# kul_rev0.net
KiCad netlist of a schematic drawn in EAGLE
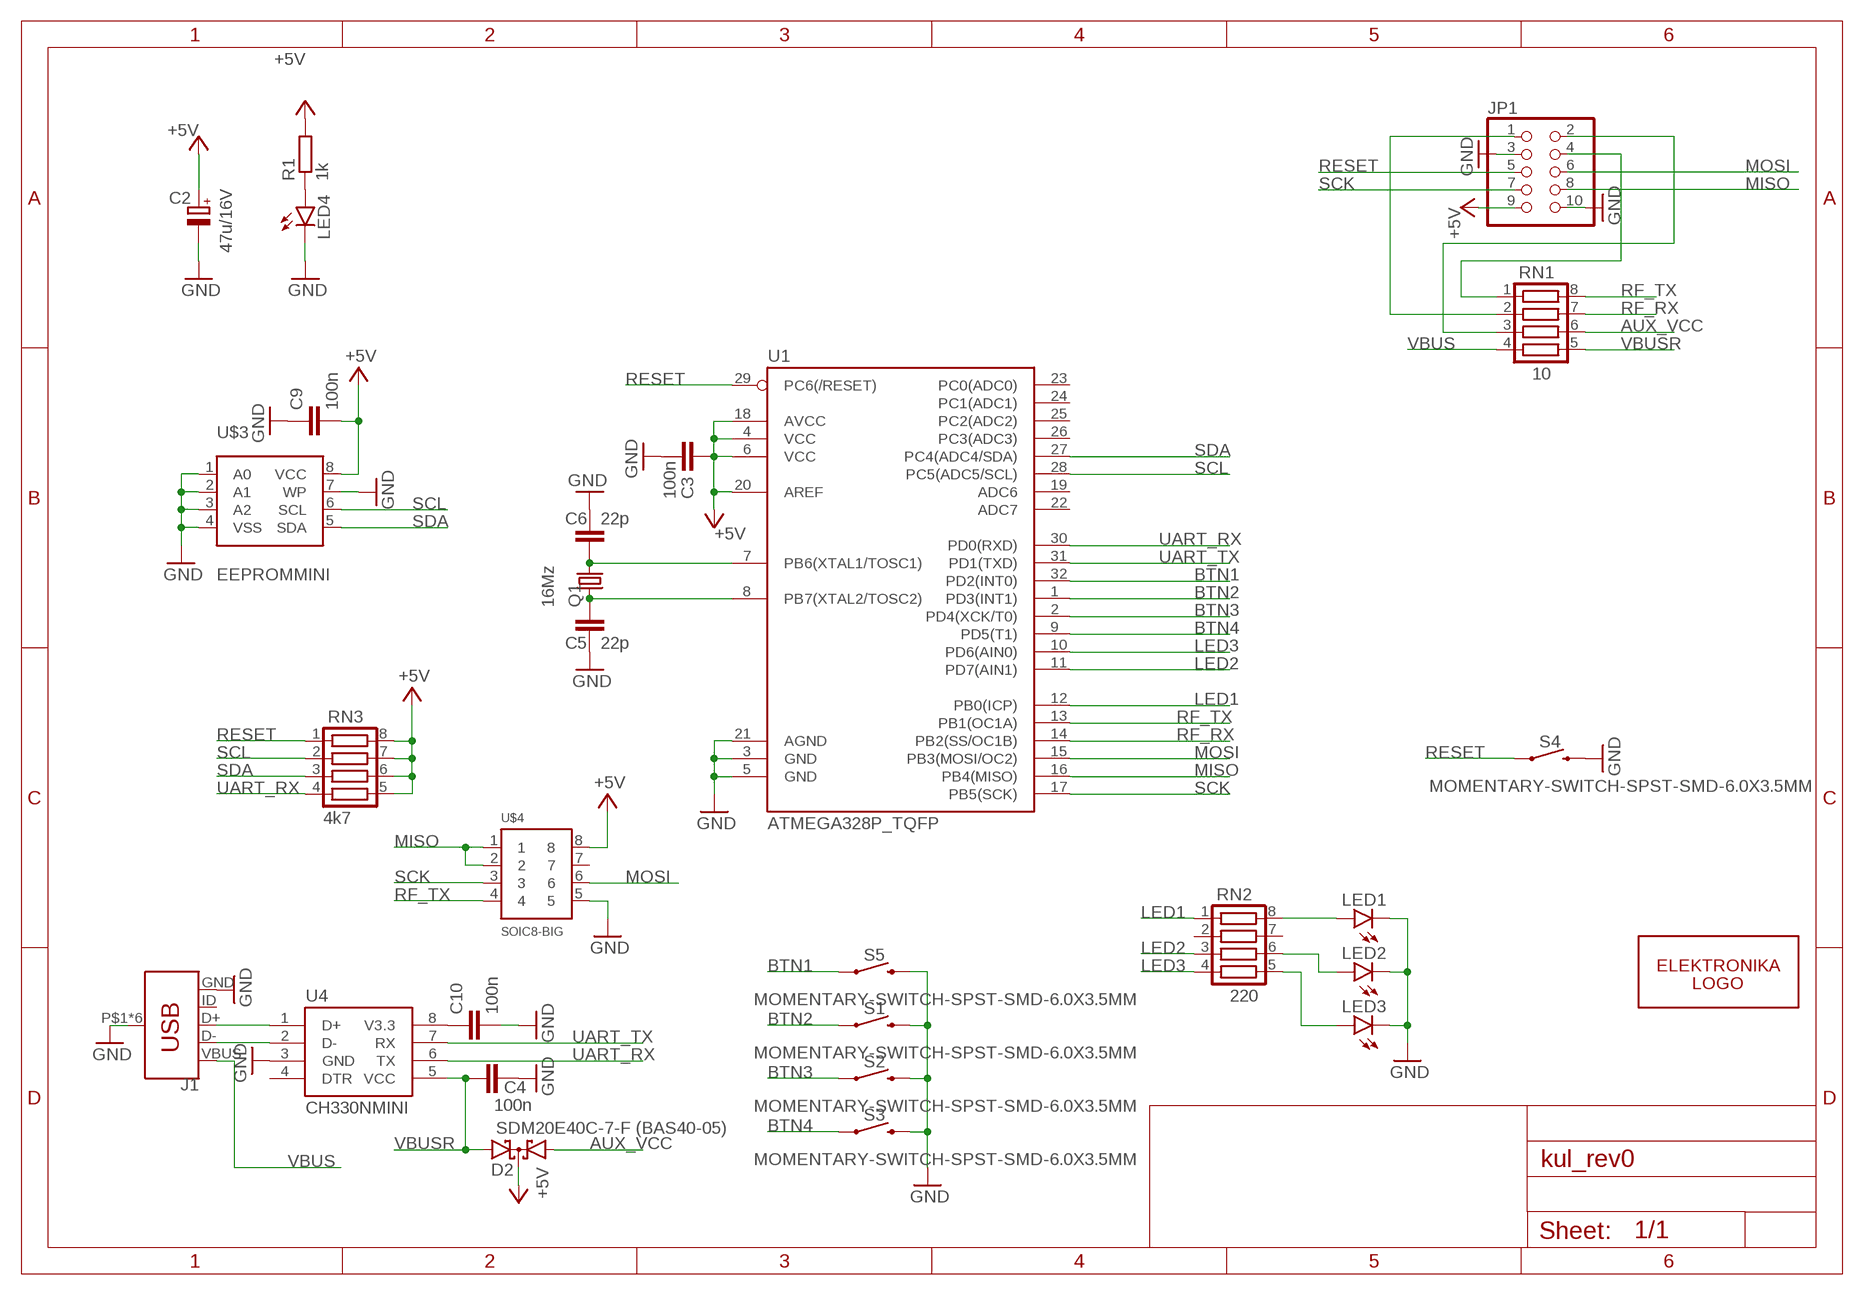
[diagram p0: schematic, sheet 1]

(export (version "E")
  (design (tool "Eeschema 10.0.6"))
  (components
    (comp (ref "C2")
      (value "47u/16V")
      (footprint "eagle-import:CT6032")
      (libsource (lib "eagle-import") (part "CPOL-EUCT6032"))
    )
    (comp (ref "C3")
      (value "100n")
      (footprint "eagle-import:C0603")
      (libsource (lib "eagle-import") (part "C-EUC0603"))
    )
    (comp (ref "C4")
      (value "100n")
      (footprint "eagle-import:C0603")
      (libsource (lib "eagle-import") (part "C-EUC0603"))
    )
    (comp (ref "C5")
      (value "22p")
      (footprint "eagle-import:C0603")
      (libsource (lib "eagle-import") (part "C-EUC0603"))
    )
    (comp (ref "C6")
      (value "22p")
      (footprint "eagle-import:C0603")
      (libsource (lib "eagle-import") (part "C-EUC0603"))
    )
    (comp (ref "C9")
      (value "100n")
      (footprint "eagle-import:C0603")
      (libsource (lib "eagle-import") (part "C-EUC0603"))
    )
    (comp (ref "C10")
      (value "100n")
      (footprint "eagle-import:C0603")
      (libsource (lib "eagle-import") (part "C-EUC0603"))
    )
    (comp (ref "D2")
      (value "SDM20E40C-7-F (BAS40-05)")
      (footprint "eagle-import:SOT23")
      (libsource (lib "eagle-import") (part "BAS40-05"))
    )
    (comp (ref "J1")
      (value "USB_MICRO-BLCSC")
      (footprint "eagle-import:C40951_USB")
      (libsource (lib "eagle-import") (part "USB_MICRO-BLCSC"))
    )
    (comp (ref "JP1")
      (value "PINHD-2X5/90")
      (footprint "eagle-import:2X05_90")
      (libsource (lib "eagle-import") (part "PINHD-2X5/90"))
    )
    (comp (ref "LED1")
      (value "LEDCHIP-LED0805")
      (footprint "eagle-import:CHIP-LED0805")
      (libsource (lib "eagle-import") (part "LEDCHIP-LED0805"))
    )
    (comp (ref "LED2")
      (value "LEDCHIP-LED0805")
      (footprint "eagle-import:CHIP-LED0805")
      (libsource (lib "eagle-import") (part "LEDCHIP-LED0805"))
    )
    (comp (ref "LED3")
      (value "LEDCHIP-LED0805")
      (footprint "eagle-import:CHIP-LED0805")
      (libsource (lib "eagle-import") (part "LEDCHIP-LED0805"))
    )
    (comp (ref "LED4")
      (value "LEDCHIP-LED0805")
      (footprint "eagle-import:CHIP-LED0805")
      (libsource (lib "eagle-import") (part "LEDCHIP-LED0805"))
    )
    (comp (ref "Q1")
      (value "16Mz")
      (footprint "eagle-import:3.2X2.5_KX-7")
      (libsource (lib "eagle-import") (part "KX-7"))
    )
    (comp (ref "R1")
      (value "1k")
      (footprint "eagle-import:R0603")
      (libsource (lib "eagle-import") (part "R-EU_R0603"))
    )
    (comp (ref "RN1")
      (value "10")
      (footprint "eagle-import:CTS742C083")
      (libsource (lib "eagle-import") (part "CTS742C083"))
    )
    (comp (ref "RN2")
      (value "220")
      (footprint "eagle-import:CTS742C083")
      (libsource (lib "eagle-import") (part "CTS742C083"))
    )
    (comp (ref "RN3")
      (value "4k7")
      (footprint "eagle-import:CTS742C083")
      (libsource (lib "eagle-import") (part "CTS742C083"))
    )
    (comp (ref "S1")
      (value "MOMENTARY-SWITCH-SPST-SMD-6.0X3.5MM")
      (footprint "eagle-import:TACTILE_SWITCH_SMD_6.0X3.5MM")
      (libsource (lib "eagle-import") (part "MOMENTARY-SWITCH-SPST-SMD-6.0X3.5MM"))
    )
    (comp (ref "S2")
      (value "MOMENTARY-SWITCH-SPST-SMD-6.0X3.5MM")
      (footprint "eagle-import:TACTILE_SWITCH_SMD_6.0X3.5MM")
      (libsource (lib "eagle-import") (part "MOMENTARY-SWITCH-SPST-SMD-6.0X3.5MM"))
    )
    (comp (ref "S3")
      (value "MOMENTARY-SWITCH-SPST-SMD-6.0X3.5MM")
      (footprint "eagle-import:TACTILE_SWITCH_SMD_6.0X3.5MM")
      (libsource (lib "eagle-import") (part "MOMENTARY-SWITCH-SPST-SMD-6.0X3.5MM"))
    )
    (comp (ref "S4")
      (value "MOMENTARY-SWITCH-SPST-SMD-6.0X3.5MM")
      (footprint "eagle-import:TACTILE_SWITCH_SMD_6.0X3.5MM")
      (libsource (lib "eagle-import") (part "MOMENTARY-SWITCH-SPST-SMD-6.0X3.5MM"))
    )
    (comp (ref "S5")
      (value "MOMENTARY-SWITCH-SPST-SMD-6.0X3.5MM")
      (footprint "eagle-import:TACTILE_SWITCH_SMD_6.0X3.5MM")
      (libsource (lib "eagle-import") (part "MOMENTARY-SWITCH-SPST-SMD-6.0X3.5MM"))
    )
    (comp (ref "U$3")
      (value "EEPROMMINI")
      (footprint "eagle-import:SOIC8_MINI")
      (libsource (lib "eagle-import") (part "EEPROMMINI"))
    )
    (comp (ref "U$4")
      (value "SOIC8-BIG")
      (footprint "eagle-import:SOIC8_BIG")
      (libsource (lib "eagle-import") (part "SOIC8-BIG"))
    )
    (comp (ref "U$6")
      (value "ELEKTRONIKA_BA_ELEBA_LOGO")
      (footprint "eagle-import:ELEKTRONIKA_BA_ELEBALOGO_ELEBALOGO_B_122")
      (libsource (lib "eagle-import") (part "ELEKTRONIKA_BA_ELEBA_LOGO"))
    )
    (comp (ref "U1")
      (value "ATMEGA328P_TQFP")
      (footprint "eagle-import:TQFP32-08")
      (libsource (lib "eagle-import") (part "ATMEGA328P_TQFP"))
    )
    (comp (ref "U4")
      (value "CH330NMINI")
      (footprint "eagle-import:SOIC8_MINI")
      (libsource (lib "eagle-import") (part "CH330NMINI"))
    )
  )
  (nets
    (net (code "1") (name "+5V") (class "Default")
      (node (ref "C2") (pin "+") (pinfunction "+_+") (pintype "passive"))
      (node (ref "C3") (pin "2") (pinfunction "2_2") (pintype "passive"))
      (node (ref "C9") (pin "2") (pinfunction "2_2") (pintype "passive"))
      (node (ref "D2") (pin "3") (pinfunction "C_3") (pintype "passive"))
      (node (ref "JP1") (pin "9") (pinfunction "9_9") (pintype "passive"))
      (node (ref "R1") (pin "2") (pinfunction "2_2") (pintype "passive"))
      (node (ref "RN3") (pin "5") (pinfunction "5_5") (pintype "passive"))
      (node (ref "RN3") (pin "6") (pinfunction "6_6") (pintype "passive"))
      (node (ref "RN3") (pin "7") (pinfunction "7_7") (pintype "passive"))
      (node (ref "RN3") (pin "8") (pinfunction "8_8") (pintype "passive"))
      (node (ref "U$3") (pin "8") (pinfunction "VCC_8") (pintype "bidirectional"))
      (node (ref "U$4") (pin "8") (pinfunction "8_8") (pintype "bidirectional"))
      (node (ref "U1") (pin "18") (pinfunction "AVCC_18") (pintype "bidirectional"))
      (node (ref "U1") (pin "20") (pinfunction "AREF_20") (pintype "bidirectional"))
      (node (ref "U1") (pin "4") (pinfunction "VCC_4") (pintype "bidirectional"))
      (node (ref "U1") (pin "6") (pinfunction "VCC_6") (pintype "bidirectional"))
    )
    (net (code "2") (name "/AUX_VCC") (class "Default")
      (node (ref "D2") (pin "1") (pinfunction "A1_1") (pintype "passive"))
      (node (ref "RN1") (pin "6") (pinfunction "6_6") (pintype "passive"))
    )
    (net (code "3") (name "/BTN1") (class "Default")
      (node (ref "S5") (pin "1") (pinfunction "1_1") (pintype "passive"))
      (node (ref "U1") (pin "32") (pinfunction "PD2(INT0)_32") (pintype "bidirectional"))
    )
    (net (code "4") (name "/BTN2") (class "Default")
      (node (ref "S1") (pin "1") (pinfunction "1_1") (pintype "passive"))
      (node (ref "U1") (pin "1") (pinfunction "PD3(INT1)_1") (pintype "bidirectional"))
    )
    (net (code "5") (name "/BTN3") (class "Default")
      (node (ref "S2") (pin "1") (pinfunction "1_1") (pintype "passive"))
      (node (ref "U1") (pin "2") (pinfunction "PD4(XCK/T0)_2") (pintype "bidirectional"))
    )
    (net (code "6") (name "/BTN4") (class "Default")
      (node (ref "S3") (pin "1") (pinfunction "1_1") (pintype "passive"))
      (node (ref "U1") (pin "9") (pinfunction "PD5(T1)_9") (pintype "bidirectional"))
    )
    (net (code "7") (name "/LED1") (class "Default")
      (node (ref "RN2") (pin "1") (pinfunction "1_1") (pintype "passive"))
      (node (ref "U1") (pin "12") (pinfunction "PB0(ICP)_12") (pintype "bidirectional"))
    )
    (net (code "8") (name "/LED2") (class "Default")
      (node (ref "RN2") (pin "3") (pinfunction "3_3") (pintype "passive"))
      (node (ref "U1") (pin "11") (pinfunction "PD7(AIN1)_11") (pintype "bidirectional"))
    )
    (net (code "9") (name "/LED3") (class "Default")
      (node (ref "RN2") (pin "4") (pinfunction "4_4") (pintype "passive"))
      (node (ref "U1") (pin "10") (pinfunction "PD6(AIN0)_10") (pintype "bidirectional"))
    )
    (net (code "10") (name "/MISO") (class "Default")
      (node (ref "JP1") (pin "8") (pinfunction "8_8") (pintype "passive"))
      (node (ref "U$4") (pin "1") (pinfunction "1_1") (pintype "bidirectional"))
      (node (ref "U$4") (pin "2") (pinfunction "2_2") (pintype "bidirectional"))
      (node (ref "U1") (pin "16") (pinfunction "PB4(MISO)_16") (pintype "bidirectional"))
    )
    (net (code "11") (name "/MOSI") (class "Default")
      (node (ref "JP1") (pin "6") (pinfunction "6_6") (pintype "passive"))
      (node (ref "U$4") (pin "6") (pinfunction "6_6") (pintype "bidirectional"))
      (node (ref "U1") (pin "15") (pinfunction "PB3(MOSI/OC2)_15") (pintype "bidirectional"))
    )
    (net (code "12") (name "/RESET") (class "Default")
      (node (ref "JP1") (pin "5") (pinfunction "5_5") (pintype "passive"))
      (node (ref "RN3") (pin "1") (pinfunction "1_1") (pintype "passive"))
      (node (ref "S4") (pin "1") (pinfunction "1_1") (pintype "passive"))
      (node (ref "U1") (pin "29") (pinfunction "PC6(/RESET)_29") (pintype "bidirectional"))
    )
    (net (code "13") (name "/RF_RX") (class "Default")
      (node (ref "RN1") (pin "7") (pinfunction "7_7") (pintype "passive"))
      (node (ref "U1") (pin "14") (pinfunction "PB2(SS/OC1B)_14") (pintype "bidirectional"))
    )
    (net (code "14") (name "/RF_TX") (class "Default")
      (node (ref "RN1") (pin "8") (pinfunction "8_8") (pintype "passive"))
      (node (ref "U$4") (pin "4") (pinfunction "4_4") (pintype "bidirectional"))
      (node (ref "U1") (pin "13") (pinfunction "PB1(OC1A)_13") (pintype "bidirectional"))
    )
    (net (code "15") (name "/SCK") (class "Default")
      (node (ref "JP1") (pin "7") (pinfunction "7_7") (pintype "passive"))
      (node (ref "U$4") (pin "3") (pinfunction "3_3") (pintype "bidirectional"))
      (node (ref "U1") (pin "17") (pinfunction "PB5(SCK)_17") (pintype "bidirectional"))
    )
    (net (code "16") (name "/SCL") (class "Default")
      (node (ref "RN3") (pin "2") (pinfunction "2_2") (pintype "passive"))
      (node (ref "U$3") (pin "6") (pinfunction "SCL_6") (pintype "bidirectional"))
      (node (ref "U1") (pin "28") (pinfunction "PC5(ADC5/SCL)_28") (pintype "bidirectional"))
    )
    (net (code "17") (name "/SDA") (class "Default")
      (node (ref "RN3") (pin "3") (pinfunction "3_3") (pintype "passive"))
      (node (ref "U$3") (pin "5") (pinfunction "SDA_5") (pintype "bidirectional"))
      (node (ref "U1") (pin "27") (pinfunction "PC4(ADC4/SDA)_27") (pintype "bidirectional"))
    )
    (net (code "18") (name "/UART_RX") (class "Default")
      (node (ref "RN3") (pin "4") (pinfunction "4_4") (pintype "passive"))
      (node (ref "U1") (pin "30") (pinfunction "PD0(RXD)_30") (pintype "bidirectional"))
      (node (ref "U4") (pin "6") (pinfunction "TX_6") (pintype "output"))
    )
    (net (code "19") (name "/UART_TX") (class "Default")
      (node (ref "U1") (pin "31") (pinfunction "PD1(TXD)_31") (pintype "bidirectional"))
      (node (ref "U4") (pin "7") (pinfunction "RX_7") (pintype "input"))
    )
    (net (code "20") (name "/VBUS") (class "Default")
      (node (ref "J1") (pin "VBUS") (pinfunction "VBUS_VBUS") (pintype "power_in"))
      (node (ref "RN1") (pin "4") (pinfunction "4_4") (pintype "passive"))
    )
    (net (code "21") (name "/VBUSR") (class "Default")
      (node (ref "C4") (pin "1") (pinfunction "1_1") (pintype "passive"))
      (node (ref "D2") (pin "2") (pinfunction "A2_2") (pintype "passive"))
      (node (ref "RN1") (pin "5") (pinfunction "5_5") (pintype "passive"))
      (node (ref "U4") (pin "5") (pinfunction "VCC_5") (pintype "power_in"))
    )
    (net (code "22") (name "GND") (class "Default")
      (node (ref "C10") (pin "2") (pinfunction "2_2") (pintype "passive"))
      (node (ref "C2") (pin "-") (pinfunction "-_-") (pintype "passive"))
      (node (ref "C3") (pin "1") (pinfunction "1_1") (pintype "passive"))
      (node (ref "C4") (pin "2") (pinfunction "2_2") (pintype "passive"))
      (node (ref "C5") (pin "2") (pinfunction "2_2") (pintype "passive"))
      (node (ref "C6") (pin "1") (pinfunction "1_1") (pintype "passive"))
      (node (ref "C9") (pin "1") (pinfunction "1_1") (pintype "passive"))
      (node (ref "J1") (pin "GND") (pinfunction "GND_GND") (pintype "power_in"))
      (node (ref "J1") (pin "P$1") (pinfunction "SHIELD_P$1") (pintype "bidirectional"))
      (node (ref "J1") (pin "P$2") (pinfunction "SHIELD_P$2") (pintype "bidirectional"))
      (node (ref "J1") (pin "P$3") (pinfunction "SHIELD_P$3") (pintype "bidirectional"))
      (node (ref "J1") (pin "P$4") (pinfunction "SHIELD_P$4") (pintype "bidirectional"))
      (node (ref "J1") (pin "SHIELD1") (pinfunction "SHIELD_SHIELD1") (pintype "bidirectional"))
      (node (ref "J1") (pin "SHIELD2") (pinfunction "SHIELD_SHIELD2") (pintype "bidirectional"))
      (node (ref "JP1") (pin "10") (pinfunction "10_10") (pintype "passive"))
      (node (ref "JP1") (pin "3") (pinfunction "3_3") (pintype "passive"))
      (node (ref "LED1") (pin "C") (pinfunction "C_C") (pintype "passive"))
      (node (ref "LED2") (pin "C") (pinfunction "C_C") (pintype "passive"))
      (node (ref "LED3") (pin "C") (pinfunction "C_C") (pintype "passive"))
      (node (ref "LED4") (pin "C") (pinfunction "C_C") (pintype "passive"))
      (node (ref "S1") (pin "2") (pinfunction "2_2") (pintype "passive"))
      (node (ref "S2") (pin "2") (pinfunction "2_2") (pintype "passive"))
      (node (ref "S3") (pin "2") (pinfunction "2_2") (pintype "passive"))
      (node (ref "S4") (pin "2") (pinfunction "2_2") (pintype "passive"))
      (node (ref "S5") (pin "2") (pinfunction "2_2") (pintype "passive"))
      (node (ref "U$3") (pin "1") (pinfunction "A0_1") (pintype "bidirectional"))
      (node (ref "U$3") (pin "2") (pinfunction "A1_2") (pintype "bidirectional"))
      (node (ref "U$3") (pin "3") (pinfunction "A2_3") (pintype "bidirectional"))
      (node (ref "U$3") (pin "4") (pinfunction "VSS_4") (pintype "bidirectional"))
      (node (ref "U$3") (pin "7") (pinfunction "WP_7") (pintype "bidirectional"))
      (node (ref "U$4") (pin "5") (pinfunction "5_5") (pintype "bidirectional"))
      (node (ref "U1") (pin "21") (pinfunction "AGND_21") (pintype "bidirectional"))
      (node (ref "U1") (pin "3") (pinfunction "GND_3") (pintype "bidirectional"))
      (node (ref "U1") (pin "5") (pinfunction "GND_5") (pintype "bidirectional"))
      (node (ref "U4") (pin "3") (pinfunction "GND_3") (pintype "power_in"))
    )
    (net (code "23") (name "Net-(JP1-Pad1)") (class "Default")
      (node (ref "JP1") (pin "1") (pinfunction "1_1") (pintype "passive"))
      (node (ref "RN1") (pin "2") (pinfunction "2_2") (pintype "passive"))
    )
    (net (code "24") (name "Net-(JP1-Pad2)") (class "Default")
      (node (ref "JP1") (pin "2") (pinfunction "2_2") (pintype "passive"))
      (node (ref "RN1") (pin "3") (pinfunction "3_3") (pintype "passive"))
    )
    (net (code "25") (name "Net-(JP1-Pad4)") (class "Default")
      (node (ref "JP1") (pin "4") (pinfunction "4_4") (pintype "passive"))
      (node (ref "RN1") (pin "1") (pinfunction "1_1") (pintype "passive"))
    )
    (net (code "26") (name "Net-(LED1-PadA)") (class "Default")
      (node (ref "LED1") (pin "A") (pinfunction "A_A") (pintype "passive"))
      (node (ref "RN2") (pin "8") (pinfunction "8_8") (pintype "passive"))
    )
    (net (code "27") (name "Net-(LED2-PadA)") (class "Default")
      (node (ref "LED2") (pin "A") (pinfunction "A_A") (pintype "passive"))
      (node (ref "RN2") (pin "6") (pinfunction "6_6") (pintype "passive"))
    )
    (net (code "28") (name "Net-(LED3-PadA)") (class "Default")
      (node (ref "LED3") (pin "A") (pinfunction "A_A") (pintype "passive"))
      (node (ref "RN2") (pin "5") (pinfunction "5_5") (pintype "passive"))
    )
    (net (code "29") (name "Net-(LED4-PadA)") (class "Default")
      (node (ref "LED4") (pin "A") (pinfunction "A_A") (pintype "passive"))
      (node (ref "R1") (pin "1") (pinfunction "1_1") (pintype "passive"))
    )
    (net (code "30") (name "Net-(Q1-2)") (class "Default")
      (node (ref "C6") (pin "2") (pinfunction "2_2") (pintype "passive"))
      (node (ref "Q1") (pin "3") (pinfunction "2_3") (pintype "passive"))
      (node (ref "U1") (pin "7") (pinfunction "PB6(XTAL1/TOSC1)_7") (pintype "bidirectional"))
    )
    (net (code "31") (name "Net-(U1-PB7(XTAL2{slash}TOSC2))") (class "Default")
      (node (ref "C5") (pin "1") (pinfunction "1_1") (pintype "passive"))
      (node (ref "Q1") (pin "1") (pinfunction "1_1") (pintype "passive"))
      (node (ref "U1") (pin "8") (pinfunction "PB7(XTAL2/TOSC2)_8") (pintype "bidirectional"))
    )
    (net (code "32") (name "Net-(U4-D+)") (class "Default")
      (node (ref "J1") (pin "D+") (pinfunction "D+_D+") (pintype "bidirectional"))
      (node (ref "U4") (pin "1") (pinfunction "D+_1") (pintype "bidirectional"))
    )
    (net (code "33") (name "Net-(U4-D-)") (class "Default")
      (node (ref "J1") (pin "D-") (pinfunction "D-_D-") (pintype "bidirectional"))
      (node (ref "U4") (pin "2") (pinfunction "D-_2") (pintype "bidirectional"))
    )
    (net (code "34") (name "Net-(U4-V3.3)") (class "Default")
      (node (ref "C10") (pin "1") (pinfunction "1_1") (pintype "passive"))
      (node (ref "U4") (pin "8") (pinfunction "V3.3_8") (pintype "power_in"))
    )
    (net (code "35") (name "unconnected-(J1-PadID)") (class "Default")
      (node (ref "J1") (pin "ID") (pinfunction "ID_ID") (pintype "bidirectional"))
    )
    (net (code "36") (name "unconnected-(RN2-Pad2)") (class "Default")
      (node (ref "RN2") (pin "2") (pinfunction "2_2") (pintype "passive"))
    )
    (net (code "37") (name "unconnected-(RN2-Pad7)") (class "Default")
      (node (ref "RN2") (pin "7") (pinfunction "7_7") (pintype "passive"))
    )
    (net (code "38") (name "unconnected-(U$4-Pad7)") (class "Default")
      (node (ref "U$4") (pin "7") (pinfunction "7_7") (pintype "bidirectional"))
    )
    (net (code "39") (name "unconnected-(U1-ADC6-Pad19)") (class "Default")
      (node (ref "U1") (pin "19") (pinfunction "ADC6_19") (pintype "bidirectional"))
    )
    (net (code "40") (name "unconnected-(U1-ADC7-Pad22)") (class "Default")
      (node (ref "U1") (pin "22") (pinfunction "ADC7_22") (pintype "bidirectional"))
    )
    (net (code "41") (name "unconnected-(U1-PC0(ADC0)-Pad23)") (class "Default")
      (node (ref "U1") (pin "23") (pinfunction "PC0(ADC0)_23") (pintype "bidirectional"))
    )
    (net (code "42") (name "unconnected-(U1-PC1(ADC1)-Pad24)") (class "Default")
      (node (ref "U1") (pin "24") (pinfunction "PC1(ADC1)_24") (pintype "bidirectional"))
    )
    (net (code "43") (name "unconnected-(U1-PC2(ADC2)-Pad25)") (class "Default")
      (node (ref "U1") (pin "25") (pinfunction "PC2(ADC2)_25") (pintype "bidirectional"))
    )
    (net (code "44") (name "unconnected-(U1-PC3(ADC3)-Pad26)") (class "Default")
      (node (ref "U1") (pin "26") (pinfunction "PC3(ADC3)_26") (pintype "bidirectional"))
    )
    (net (code "45") (name "unconnected-(U4-DTR-Pad4)") (class "Default")
      (node (ref "U4") (pin "4") (pinfunction "DTR_4") (pintype "bidirectional"))
    )
  )
)
